# main.net
KiCad netlist of a schematic drawn in EAGLE
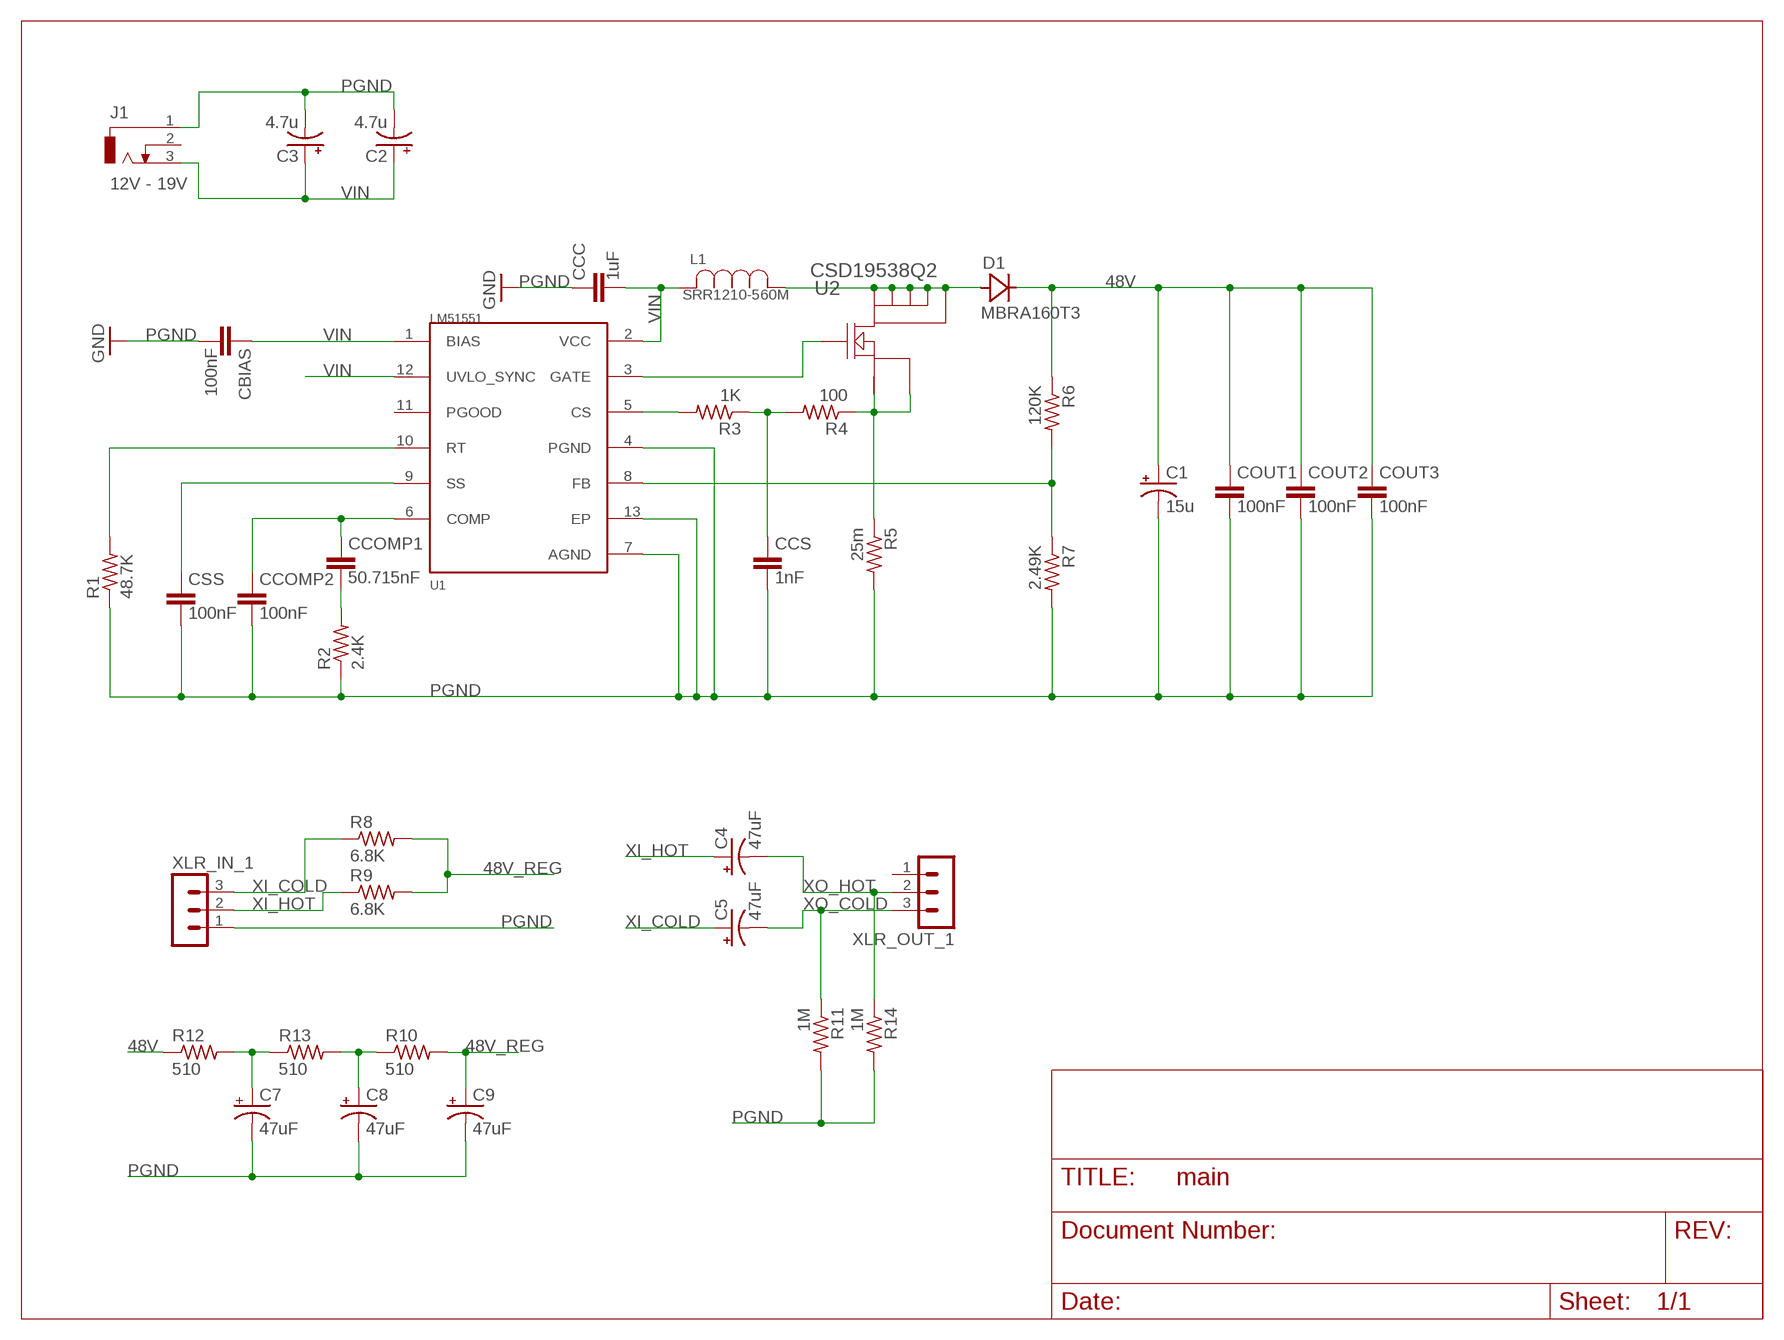
[diagram p0: schematic, sheet 1]

(export (version "E")
  (design (tool "Eeschema 10.0.6"))
  (components
    (comp (ref "C1")
      (value "15u")
      (footprint "eagle-import:CT7343")
      (libsource (lib "eagle-import") (part "CPOL-USCT7343"))
    )
    (comp (ref "C2")
      (value "4.7u")
      (footprint "eagle-import:CT7343")
      (libsource (lib "eagle-import") (part "CPOL-USCT7343"))
    )
    (comp (ref "C3")
      (value "4.7u")
      (footprint "eagle-import:CT7343")
      (libsource (lib "eagle-import") (part "CPOL-USCT7343"))
    )
    (comp (ref "C4")
      (value "47uF")
      (footprint "eagle-import:153CLV-0810")
      (libsource (lib "eagle-import") (part "CPOL-US153CLV-0810"))
    )
    (comp (ref "C5")
      (value "47uF")
      (footprint "eagle-import:153CLV-0810")
      (libsource (lib "eagle-import") (part "CPOL-US153CLV-0810"))
    )
    (comp (ref "C7")
      (value "47uF")
      (footprint "eagle-import:153CLV-0810")
      (libsource (lib "eagle-import") (part "CPOL-US153CLV-0810"))
    )
    (comp (ref "C8")
      (value "47uF")
      (footprint "eagle-import:153CLV-0810")
      (libsource (lib "eagle-import") (part "CPOL-US153CLV-0810"))
    )
    (comp (ref "C9")
      (value "47uF")
      (footprint "eagle-import:153CLV-0810")
      (libsource (lib "eagle-import") (part "CPOL-US153CLV-0810"))
    )
    (comp (ref "CBIAS")
      (value "100nF")
      (footprint "eagle-import:C0805")
      (libsource (lib "eagle-import") (part "C-EUC0805"))
    )
    (comp (ref "CCC")
      (value "1uF")
      (footprint "eagle-import:C0805")
      (libsource (lib "eagle-import") (part "C-EUC0805"))
    )
    (comp (ref "CCOMP1")
      (value "50.715nF")
      (footprint "eagle-import:C0805")
      (libsource (lib "eagle-import") (part "C-EUC0805"))
    )
    (comp (ref "CCOMP2")
      (value "100nF")
      (footprint "eagle-import:C0805")
      (libsource (lib "eagle-import") (part "C-EUC0805"))
    )
    (comp (ref "CCS")
      (value "1nF")
      (footprint "eagle-import:C0805")
      (libsource (lib "eagle-import") (part "C-EUC0805"))
    )
    (comp (ref "COUT1")
      (value "100nF")
      (footprint "eagle-import:C0805")
      (libsource (lib "eagle-import") (part "C-EUC0805"))
    )
    (comp (ref "COUT2")
      (value "100nF")
      (footprint "eagle-import:C0805")
      (libsource (lib "eagle-import") (part "C-EUC0805"))
    )
    (comp (ref "COUT3")
      (value "100nF")
      (footprint "eagle-import:C0805")
      (libsource (lib "eagle-import") (part "C-EUC0805"))
    )
    (comp (ref "CSS")
      (value "100nF")
      (footprint "eagle-import:C0805")
      (libsource (lib "eagle-import") (part "C-EUC0805"))
    )
    (comp (ref "D1")
      (value "MBRA160T3")
      (footprint "eagle-import:SMA")
      (libsource (lib "eagle-import") (part "MBRA340T3"))
    )
    (comp (ref "J1")
      (value "12V - 19V")
      (footprint "eagle-import:DCJ0303")
      (libsource (lib "eagle-import") (part "DCJ0303"))
    )
    (comp (ref "L1")
      (value "SRR1210-560M")
      (footprint "eagle-import:IND_BOURNS_SRR1210")
      (libsource (lib "eagle-import") (part "SRR1210-560M"))
    )
    (comp (ref "R1")
      (value "48.7K")
      (footprint "eagle-import:R0805")
      (libsource (lib "eagle-import") (part "R-US_R0805"))
    )
    (comp (ref "R2")
      (value "2.4K")
      (footprint "eagle-import:R0805")
      (libsource (lib "eagle-import") (part "R-US_R0805"))
    )
    (comp (ref "R3")
      (value "1K")
      (footprint "eagle-import:R0805")
      (libsource (lib "eagle-import") (part "R-US_R0805"))
    )
    (comp (ref "R4")
      (value "100")
      (footprint "eagle-import:R0805")
      (libsource (lib "eagle-import") (part "R-US_R0805"))
    )
    (comp (ref "R5")
      (value "25m")
      (footprint "eagle-import:R1206")
      (libsource (lib "eagle-import") (part "R-US_R1206"))
    )
    (comp (ref "R6")
      (value "120K")
      (footprint "eagle-import:R0805")
      (libsource (lib "eagle-import") (part "R-US_R0805"))
    )
    (comp (ref "R7")
      (value "2.49K")
      (footprint "eagle-import:R0805")
      (libsource (lib "eagle-import") (part "R-US_R0805"))
    )
    (comp (ref "R8")
      (value "6.8K")
      (footprint "eagle-import:R1206")
      (libsource (lib "eagle-import") (part "R-US_R1206"))
    )
    (comp (ref "R9")
      (value "6.8K")
      (footprint "eagle-import:R1206")
      (libsource (lib "eagle-import") (part "R-US_R1206"))
    )
    (comp (ref "R10")
      (value "510")
      (footprint "eagle-import:R1206")
      (libsource (lib "eagle-import") (part "R-US_R1206"))
    )
    (comp (ref "R11")
      (value "1M")
      (footprint "eagle-import:R0805")
      (libsource (lib "eagle-import") (part "R-US_R0805"))
    )
    (comp (ref "R12")
      (value "510")
      (footprint "eagle-import:R1206")
      (libsource (lib "eagle-import") (part "R-US_R1206"))
    )
    (comp (ref "R13")
      (value "510")
      (footprint "eagle-import:R1206")
      (libsource (lib "eagle-import") (part "R-US_R1206"))
    )
    (comp (ref "R14")
      (value "1M")
      (footprint "eagle-import:R0805")
      (libsource (lib "eagle-import") (part "R-US_R0805"))
    )
    (comp (ref "U1")
      (value "LM51551")
      (footprint "eagle-import:SON45P300X300X80-13N")
      (libsource (lib "eagle-import") (part "LM51551"))
    )
    (comp (ref "U2")
      (value "CSD19538Q2")
      (footprint "eagle-import:DQK0006C")
      (libsource (lib "eagle-import") (part "CSD19538Q2"))
    )
    (comp (ref "XLR_IN_1")
      (value "MA03-1")
      (footprint "eagle-import:MA03-1")
      (libsource (lib "eagle-import") (part "MA03-1"))
    )
    (comp (ref "XLR_OUT_1")
      (value "MA03-1")
      (footprint "eagle-import:MA03-1")
      (libsource (lib "eagle-import") (part "MA03-1"))
    )
  )
  (nets
    (net (code "1") (name "/48V") (class "Default")
      (node (ref "C1") (pin "+") (pinfunction "+_+") (pintype "passive"))
      (node (ref "COUT1") (pin "1") (pinfunction "1_1") (pintype "passive"))
      (node (ref "COUT2") (pin "1") (pinfunction "1_1") (pintype "passive"))
      (node (ref "COUT3") (pin "1") (pinfunction "1_1") (pintype "passive"))
      (node (ref "D1") (pin "C") (pinfunction "C_C") (pintype "passive"))
      (node (ref "R12") (pin "1") (pinfunction "1_1") (pintype "passive"))
      (node (ref "R6") (pin "1") (pinfunction "1_1") (pintype "passive"))
    )
    (net (code "2") (name "/48V_REG") (class "Default")
      (node (ref "C9") (pin "+") (pinfunction "+_+") (pintype "passive"))
      (node (ref "R10") (pin "2") (pinfunction "2_2") (pintype "passive"))
      (node (ref "R8") (pin "2") (pinfunction "2_2") (pintype "passive"))
      (node (ref "R9") (pin "2") (pinfunction "2_2") (pintype "passive"))
    )
    (net (code "3") (name "/VIN") (class "Default")
      (node (ref "C2") (pin "+") (pinfunction "+_+") (pintype "passive"))
      (node (ref "C3") (pin "+") (pinfunction "+_+") (pintype "passive"))
      (node (ref "CBIAS") (pin "1") (pinfunction "1_1") (pintype "passive"))
      (node (ref "CCC") (pin "2") (pinfunction "2_2") (pintype "passive"))
      (node (ref "J1") (pin "3") (pinfunction "3_3") (pintype "passive"))
      (node (ref "L1") (pin "2") (pinfunction "2_2") (pintype "passive"))
      (node (ref "U1") (pin "1") (pinfunction "BIAS_1") (pintype "power_in"))
      (node (ref "U1") (pin "12") (pinfunction "UVLO_SYNC_12") (pintype "input"))
      (node (ref "U1") (pin "2") (pinfunction "VCC_2") (pintype "power_in"))
    )
    (net (code "4") (name "/XI_COLD") (class "Default")
      (node (ref "C5") (pin "+") (pinfunction "+_+") (pintype "passive"))
      (node (ref "R8") (pin "1") (pinfunction "1_1") (pintype "passive"))
      (node (ref "XLR_IN_1") (pin "3") (pinfunction "3_3") (pintype "passive"))
    )
    (net (code "5") (name "/XI_HOT") (class "Default")
      (node (ref "C4") (pin "+") (pinfunction "+_+") (pintype "passive"))
      (node (ref "R9") (pin "1") (pinfunction "1_1") (pintype "passive"))
      (node (ref "XLR_IN_1") (pin "2") (pinfunction "2_2") (pintype "passive"))
    )
    (net (code "6") (name "/XO_COLD") (class "Default")
      (node (ref "C5") (pin "-") (pinfunction "-_-") (pintype "passive"))
      (node (ref "R11") (pin "1") (pinfunction "1_1") (pintype "passive"))
      (node (ref "XLR_OUT_1") (pin "3") (pinfunction "3_3") (pintype "passive"))
    )
    (net (code "7") (name "/XO_HOT") (class "Default")
      (node (ref "C4") (pin "-") (pinfunction "-_-") (pintype "passive"))
      (node (ref "R14") (pin "1") (pinfunction "1_1") (pintype "passive"))
      (node (ref "XLR_OUT_1") (pin "2") (pinfunction "2_2") (pintype "passive"))
    )
    (net (code "8") (name "GND") (class "Default")
      (node (ref "C1") (pin "-") (pinfunction "-_-") (pintype "passive"))
      (node (ref "C2") (pin "-") (pinfunction "-_-") (pintype "passive"))
      (node (ref "C3") (pin "-") (pinfunction "-_-") (pintype "passive"))
      (node (ref "C7") (pin "-") (pinfunction "-_-") (pintype "passive"))
      (node (ref "C8") (pin "-") (pinfunction "-_-") (pintype "passive"))
      (node (ref "C9") (pin "-") (pinfunction "-_-") (pintype "passive"))
      (node (ref "CBIAS") (pin "2") (pinfunction "2_2") (pintype "passive"))
      (node (ref "CCC") (pin "1") (pinfunction "1_1") (pintype "passive"))
      (node (ref "CCOMP2") (pin "2") (pinfunction "2_2") (pintype "passive"))
      (node (ref "CCS") (pin "2") (pinfunction "2_2") (pintype "passive"))
      (node (ref "COUT1") (pin "2") (pinfunction "2_2") (pintype "passive"))
      (node (ref "COUT2") (pin "2") (pinfunction "2_2") (pintype "passive"))
      (node (ref "COUT3") (pin "2") (pinfunction "2_2") (pintype "passive"))
      (node (ref "CSS") (pin "2") (pinfunction "2_2") (pintype "passive"))
      (node (ref "J1") (pin "1") (pinfunction "1_1") (pintype "passive"))
      (node (ref "R1") (pin "1") (pinfunction "1_1") (pintype "passive"))
      (node (ref "R11") (pin "2") (pinfunction "2_2") (pintype "passive"))
      (node (ref "R14") (pin "2") (pinfunction "2_2") (pintype "passive"))
      (node (ref "R2") (pin "1") (pinfunction "1_1") (pintype "passive"))
      (node (ref "R5") (pin "2") (pinfunction "2_2") (pintype "passive"))
      (node (ref "R7") (pin "2") (pinfunction "2_2") (pintype "passive"))
      (node (ref "U1") (pin "13") (pinfunction "EP_13") (pintype "passive"))
      (node (ref "U1") (pin "4") (pinfunction "PGND_4") (pintype "power_in"))
      (node (ref "U1") (pin "7") (pinfunction "AGND_7") (pintype "power_in"))
      (node (ref "XLR_IN_1") (pin "1") (pinfunction "1_1") (pintype "passive"))
    )
    (net (code "9") (name "Net-(C7-Pad+)") (class "Default")
      (node (ref "C7") (pin "+") (pinfunction "+_+") (pintype "passive"))
      (node (ref "R12") (pin "2") (pinfunction "2_2") (pintype "passive"))
      (node (ref "R13") (pin "1") (pinfunction "1_1") (pintype "passive"))
    )
    (net (code "10") (name "Net-(C8-Pad+)") (class "Default")
      (node (ref "C8") (pin "+") (pinfunction "+_+") (pintype "passive"))
      (node (ref "R10") (pin "1") (pinfunction "1_1") (pintype "passive"))
      (node (ref "R13") (pin "2") (pinfunction "2_2") (pintype "passive"))
    )
    (net (code "11") (name "Net-(CCOMP1-Pad2)") (class "Default")
      (node (ref "CCOMP1") (pin "2") (pinfunction "2_2") (pintype "passive"))
      (node (ref "R2") (pin "2") (pinfunction "2_2") (pintype "passive"))
    )
    (net (code "12") (name "Net-(CCS-Pad1)") (class "Default")
      (node (ref "CCS") (pin "1") (pinfunction "1_1") (pintype "passive"))
      (node (ref "R3") (pin "1") (pinfunction "1_1") (pintype "passive"))
      (node (ref "R4") (pin "2") (pinfunction "2_2") (pintype "passive"))
    )
    (net (code "13") (name "Net-(U1-COMP)") (class "Default")
      (node (ref "CCOMP1") (pin "1") (pinfunction "1_1") (pintype "passive"))
      (node (ref "CCOMP2") (pin "1") (pinfunction "1_1") (pintype "passive"))
      (node (ref "U1") (pin "6") (pinfunction "COMP_6") (pintype "output"))
    )
    (net (code "14") (name "Net-(U1-CS)") (class "Default")
      (node (ref "R3") (pin "2") (pinfunction "2_2") (pintype "passive"))
      (node (ref "U1") (pin "5") (pinfunction "CS_5") (pintype "input"))
    )
    (net (code "15") (name "Net-(U1-FB)") (class "Default")
      (node (ref "R6") (pin "2") (pinfunction "2_2") (pintype "passive"))
      (node (ref "R7") (pin "1") (pinfunction "1_1") (pintype "passive"))
      (node (ref "U1") (pin "8") (pinfunction "FB_8") (pintype "input"))
    )
    (net (code "16") (name "Net-(U1-GATE)") (class "Default")
      (node (ref "U1") (pin "3") (pinfunction "GATE_3") (pintype "output"))
      (node (ref "U2") (pin "3") (pinfunction "GATE_3") (pintype "passive"))
    )
    (net (code "17") (name "Net-(U1-RT)") (class "Default")
      (node (ref "R1") (pin "2") (pinfunction "2_2") (pintype "passive"))
      (node (ref "U1") (pin "10") (pinfunction "RT_10") (pintype "input"))
    )
    (net (code "18") (name "Net-(U1-SS)") (class "Default")
      (node (ref "CSS") (pin "1") (pinfunction "1_1") (pintype "passive"))
      (node (ref "U1") (pin "9") (pinfunction "SS_9") (pintype "input"))
    )
    (net (code "19") (name "Net-(U2-DRAIN_1)") (class "Default")
      (node (ref "D1") (pin "A") (pinfunction "A_A") (pintype "passive"))
      (node (ref "L1") (pin "1") (pinfunction "1_1") (pintype "passive"))
      (node (ref "U2") (pin "1") (pinfunction "DRAIN_1_1") (pintype "passive"))
      (node (ref "U2") (pin "2") (pinfunction "DRAIN_2_2") (pintype "passive"))
      (node (ref "U2") (pin "5") (pinfunction "DRAIN_3_5") (pintype "passive"))
      (node (ref "U2") (pin "6") (pinfunction "DRAIN_4_6") (pintype "passive"))
      (node (ref "U2") (pin "8") (pinfunction "DRAIN_5_8") (pintype "passive"))
    )
    (net (code "20") (name "Net-(U2-SOURCE_1)") (class "Default")
      (node (ref "R4") (pin "1") (pinfunction "1_1") (pintype "passive"))
      (node (ref "R5") (pin "1") (pinfunction "1_1") (pintype "passive"))
      (node (ref "U2") (pin "4") (pinfunction "SOURCE_2_4") (pintype "passive"))
      (node (ref "U2") (pin "7") (pinfunction "SOURCE_1_7") (pintype "passive"))
    )
    (net (code "21") (name "unconnected-(J1-Pad2)") (class "Default")
      (node (ref "J1") (pin "2") (pinfunction "2_2") (pintype "passive"))
    )
    (net (code "22") (name "unconnected-(U1-PGOOD-Pad11)") (class "Default")
      (node (ref "U1") (pin "11") (pinfunction "PGOOD_11") (pintype "output"))
    )
    (net (code "23") (name "unconnected-(XLR_OUT_1-Pad1)") (class "Default")
      (node (ref "XLR_OUT_1") (pin "1") (pinfunction "1_1") (pintype "passive"))
    )
  )
)
